# smallversion.net
KiCad netlist of a schematic drawn in EAGLE
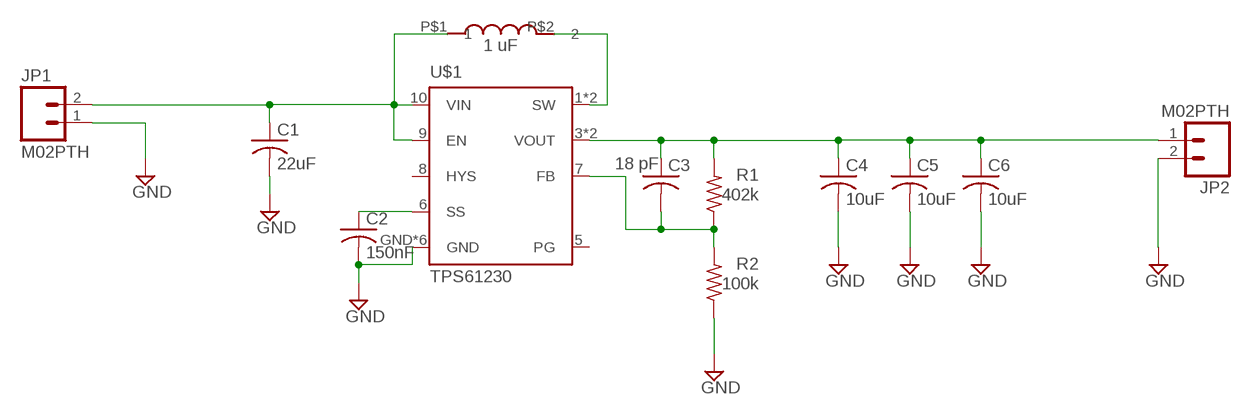
[diagram p0: schematic, sheet 1]

(export (version "E")
  (design (tool "Eeschema 10.0.6"))
  (components
    (comp (ref "C1")
      (value "22uF")
      (footprint "eagle-import:C1206")
      (libsource (lib "eagle-import") (part "resistor_C-USC1206"))
    )
    (comp (ref "C2")
      (value "150nF")
      (footprint "eagle-import:C0603K")
      (libsource (lib "eagle-import") (part "C-USC0603K"))
    )
    (comp (ref "C3")
      (value "18 pF")
      (footprint "eagle-import:C0603K")
      (libsource (lib "eagle-import") (part "resistor_C-USC0603K"))
    )
    (comp (ref "C4")
      (value "10uF")
      (footprint "eagle-import:C0805K")
      (libsource (lib "eagle-import") (part "resistor_C-USC0805K"))
    )
    (comp (ref "C5")
      (value "10uF")
      (footprint "eagle-import:C0805K")
      (libsource (lib "eagle-import") (part "resistor_C-USC0805K"))
    )
    (comp (ref "C6")
      (value "10uF")
      (footprint "eagle-import:C0805K")
      (libsource (lib "eagle-import") (part "resistor_C-USC0805K"))
    )
    (comp (ref "JP1")
      (value "M02PTH")
      (footprint "eagle-import:1X02")
      (libsource (lib "eagle-import") (part "M02PTH"))
    )
    (comp (ref "JP2")
      (value "M02PTH")
      (footprint "eagle-import:1X02")
      (libsource (lib "eagle-import") (part "M02PTH"))
    )
    (comp (ref "R1")
      (value "402k")
      (footprint "eagle-import:R0603")
      (libsource (lib "eagle-import") (part "R-US_R0603"))
    )
    (comp (ref "R2")
      (value "100k")
      (footprint "eagle-import:R0603")
      (libsource (lib "eagle-import") (part "R-US_R0603"))
    )
    (comp (ref "U$1")
      (value "TPS61230")
      (footprint "eagle-import:DRC-S-PVSON-N11")
      (libsource (lib "eagle-import") (part "TPS61230"))
    )
    (comp (ref "U$3")
      (value "SRU1028")
      (footprint "eagle-import:SRU1028")
      (libsource (lib "eagle-import") (part "SRU1028"))
    )
  )
  (nets
    (net (code "1") (name "/PG") (class "Default")
      (node (ref "U$1") (pin "5") (pinfunction "PG_5") (pintype "power_in"))
    )
    (net (code "2") (name "GND") (class "Default")
      (node (ref "C1") (pin "2") (pinfunction "2_2") (pintype "passive"))
      (node (ref "C2") (pin "2") (pinfunction "2_2") (pintype "passive"))
      (node (ref "C4") (pin "2") (pinfunction "2_2") (pintype "passive"))
      (node (ref "C5") (pin "2") (pinfunction "2_2") (pintype "passive"))
      (node (ref "C6") (pin "2") (pinfunction "2_2") (pintype "passive"))
      (node (ref "JP1") (pin "1") (pinfunction "1_1") (pintype "passive"))
      (node (ref "JP2") (pin "2") (pinfunction "2_2") (pintype "passive"))
      (node (ref "R2") (pin "1") (pinfunction "1_1") (pintype "passive"))
      (node (ref "U$1") (pin "GND") (pinfunction "GND_GND") (pintype "power_in"))
      (node (ref "U$1") (pin "GND@1") (pinfunction "GND_GND@1") (pintype "power_in"))
      (node (ref "U$1") (pin "GND@2") (pinfunction "GND_GND@2") (pintype "power_in"))
      (node (ref "U$1") (pin "GND@3") (pinfunction "GND_GND@3") (pintype "power_in"))
      (node (ref "U$1") (pin "GND@4") (pinfunction "GND_GND@4") (pintype "power_in"))
      (node (ref "U$1") (pin "GND@5") (pinfunction "GND_GND@5") (pintype "power_in"))
    )
    (net (code "3") (name "Net-(C3-Pad1)") (class "Default")
      (node (ref "C3") (pin "1") (pinfunction "1_1") (pintype "passive"))
      (node (ref "C4") (pin "1") (pinfunction "1_1") (pintype "passive"))
      (node (ref "C5") (pin "1") (pinfunction "1_1") (pintype "passive"))
      (node (ref "C6") (pin "1") (pinfunction "1_1") (pintype "passive"))
      (node (ref "JP2") (pin "1") (pinfunction "1_1") (pintype "passive"))
      (node (ref "R1") (pin "2") (pinfunction "2_2") (pintype "passive"))
      (node (ref "U$1") (pin "3") (pinfunction "VOUT_3") (pintype "passive"))
      (node (ref "U$1") (pin "4") (pinfunction "VOUT_4") (pintype "passive"))
    )
    (net (code "4") (name "Net-(U$1-EN)") (class "Default")
      (node (ref "C1") (pin "1") (pinfunction "1_1") (pintype "passive"))
      (node (ref "JP1") (pin "2") (pinfunction "2_2") (pintype "passive"))
      (node (ref "U$1") (pin "10") (pinfunction "VIN_10") (pintype "input"))
      (node (ref "U$1") (pin "9") (pinfunction "EN_9") (pintype "input"))
      (node (ref "U$3") (pin "P$1") (pinfunction "1_P$1") (pintype "bidirectional"))
    )
    (net (code "5") (name "Net-(U$1-FB)") (class "Default")
      (node (ref "C3") (pin "2") (pinfunction "2_2") (pintype "passive"))
      (node (ref "R1") (pin "1") (pinfunction "1_1") (pintype "passive"))
      (node (ref "R2") (pin "2") (pinfunction "2_2") (pintype "passive"))
      (node (ref "U$1") (pin "7") (pinfunction "FB_7") (pintype "input"))
    )
    (net (code "6") (name "Net-(U$1-SS)") (class "Default")
      (node (ref "C2") (pin "1") (pinfunction "1_1") (pintype "passive"))
      (node (ref "U$1") (pin "6") (pinfunction "SS_6") (pintype "input"))
    )
    (net (code "7") (name "Net-(U$3-2)") (class "Default")
      (node (ref "U$1") (pin "1") (pinfunction "SW_1") (pintype "input"))
      (node (ref "U$1") (pin "2") (pinfunction "SW_2") (pintype "input"))
      (node (ref "U$3") (pin "P$2") (pinfunction "2_P$2") (pintype "bidirectional"))
    )
    (net (code "8") (name "unconnected-(U$1-HYS-Pad8)") (class "Default")
      (node (ref "U$1") (pin "8") (pinfunction "HYS_8") (pintype "input"))
    )
  )
)
